# LMNC_VCO_-_v1_2.net
KiCad netlist of a schematic drawn in EAGLE
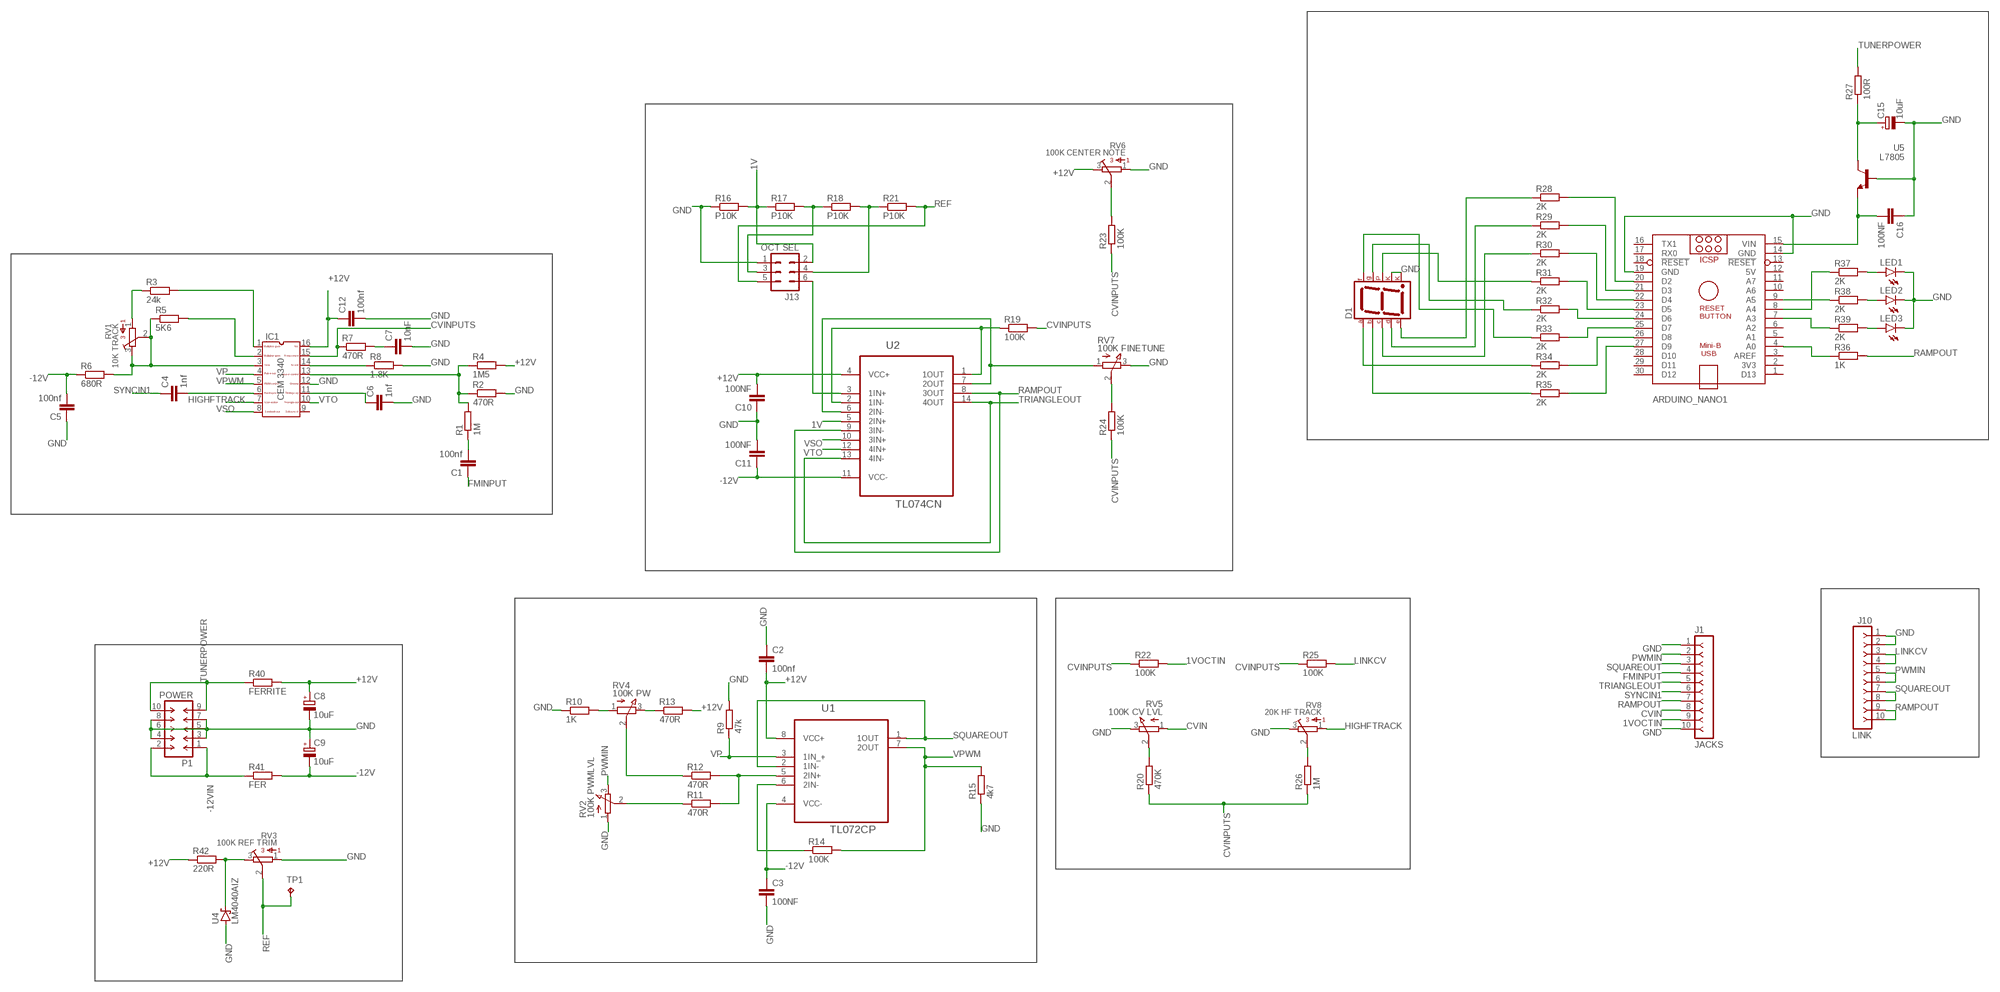
[diagram p0: schematic, sheet 1]

(export (version "E")
  (design (tool "Eeschema 10.0.6"))
  (components
    (comp (ref "ARDUINO_NANO1")
      (value "ARDUINO_NANO")
      (footprint "eagle-import:ARDUINO_NANO")
      (libsource (lib "eagle-import") (part "ARDUINO_NANO"))
    )
    (comp (ref "C1")
      (value "100nf")
      (footprint "eagle-import:C2.5-3")
      (libsource (lib "eagle-import") (part "C2,5-3"))
    )
    (comp (ref "C2")
      (value "100nf")
      (footprint "eagle-import:C2.5-3")
      (libsource (lib "eagle-import") (part "C2,5-3"))
    )
    (comp (ref "C3")
      (value "100NF")
      (footprint "eagle-import:C2.5-3")
      (libsource (lib "eagle-import") (part "C2,5-3"))
    )
    (comp (ref "C4")
      (value "1nf")
      (footprint "eagle-import:C2.5-3")
      (libsource (lib "eagle-import") (part "C2,5-3"))
    )
    (comp (ref "C5")
      (value "100nf")
      (footprint "eagle-import:C2.5-3")
      (libsource (lib "eagle-import") (part "C2,5-3"))
    )
    (comp (ref "C6")
      (value "1nf")
      (footprint "eagle-import:C2.5-3")
      (libsource (lib "eagle-import") (part "C2,5-3"))
    )
    (comp (ref "C7")
      (value "10nF")
      (footprint "eagle-import:C2.5-3")
      (libsource (lib "eagle-import") (part "C2,5-3"))
    )
    (comp (ref "C8")
      (value "10uF")
      (footprint "eagle-import:E2,5-5")
      (libsource (lib "eagle-import") (part "CPOL-EUE2.5-5"))
    )
    (comp (ref "C9")
      (value "10uF")
      (footprint "eagle-import:E2,5-5")
      (libsource (lib "eagle-import") (part "CPOL-EUE2.5-5"))
    )
    (comp (ref "C10")
      (value "100NF")
      (footprint "eagle-import:C2.5-3")
      (libsource (lib "eagle-import") (part "C2,5-3"))
    )
    (comp (ref "C11")
      (value "100NF")
      (footprint "eagle-import:C2.5-3")
      (libsource (lib "eagle-import") (part "C2,5-3"))
    )
    (comp (ref "C12")
      (value "100nf")
      (footprint "eagle-import:C2.5-3")
      (libsource (lib "eagle-import") (part "C2,5-3"))
    )
    (comp (ref "C15")
      (value "10uF")
      (footprint "eagle-import:E2,5-5")
      (libsource (lib "eagle-import") (part "CPOL-EUE2.5-5"))
    )
    (comp (ref "C16")
      (value "100NF")
      (footprint "eagle-import:C2.5-3")
      (libsource (lib "eagle-import") (part "C2,5-3"))
    )
    (comp (ref "D1")
      (value "7SEG-CK")
      (footprint "eagle-import:7SEG-13")
      (libsource (lib "eagle-import") (part "7SEG-CK"))
    )
    (comp (ref "IC1")
      (value "CEM3340")
      (footprint "eagle-import:DIL16")
      (libsource (lib "eagle-import") (part "CEM3340"))
    )
    (comp (ref "J1")
      (value "JACKS")
      (footprint "eagle-import:SIP-100-10-32Y")
      (fields (field (name "SPICEPREFIX") "X"))
      (libsource (lib "eagle-import") (part "F-1X10-SIP-100-32Y"))
    )
    (comp (ref "J10")
      (value "LINK")
      (footprint "eagle-import:SIP-100-10-32Y")
      (libsource (lib "eagle-import") (part "F-1X10-SIP-100-32Y"))
    )
    (comp (ref "J13")
      (value "OCT SEL")
      (footprint "eagle-import:MA03-2")
      (libsource (lib "eagle-import") (part "MA03-2"))
    )
    (comp (ref "LED1")
      (value "LED3MM")
      (footprint "eagle-import:LED3MM")
      (libsource (lib "eagle-import") (part "LED3MM"))
    )
    (comp (ref "LED2")
      (value "LED3MM")
      (footprint "eagle-import:LED3MM")
      (libsource (lib "eagle-import") (part "LED3MM"))
    )
    (comp (ref "LED3")
      (value "LED3MM")
      (footprint "eagle-import:LED3MM")
      (libsource (lib "eagle-import") (part "LED3MM"))
    )
    (comp (ref "P1")
      (value "POWER")
      (footprint "eagle-import:DIL-100-2X05")
      (libsource (lib "eagle-import") (part "M-2X05-DIL-100"))
    )
    (comp (ref "R1")
      (value "1M")
      (footprint "eagle-import:0207_10")
      (libsource (lib "eagle-import") (part "R-EU_0207/10"))
    )
    (comp (ref "R2")
      (value "470R")
      (footprint "eagle-import:0207_10")
      (libsource (lib "eagle-import") (part "R-EU_0207/10"))
    )
    (comp (ref "R3")
      (value "24k")
      (footprint "eagle-import:0207_10")
      (libsource (lib "eagle-import") (part "R-EU_0207/10"))
    )
    (comp (ref "R4")
      (value "1M5")
      (footprint "eagle-import:0207_10")
      (libsource (lib "eagle-import") (part "R-EU_0207/10"))
    )
    (comp (ref "R5")
      (value "5K6")
      (footprint "eagle-import:0207_10")
      (libsource (lib "eagle-import") (part "R-EU_0207/10"))
    )
    (comp (ref "R6")
      (value "680R")
      (footprint "eagle-import:0207_10")
      (libsource (lib "eagle-import") (part "R-EU_0207/10"))
    )
    (comp (ref "R7")
      (value "470R")
      (footprint "eagle-import:0207_10")
      (libsource (lib "eagle-import") (part "R-EU_0207/10"))
    )
    (comp (ref "R8")
      (value "1.8K")
      (footprint "eagle-import:0207_10")
      (libsource (lib "eagle-import") (part "R-EU_0207/10"))
    )
    (comp (ref "R9")
      (value "47k")
      (footprint "eagle-import:0207_10")
      (libsource (lib "eagle-import") (part "R-EU_0207/10"))
    )
    (comp (ref "R10")
      (value "1K")
      (footprint "eagle-import:0207_10")
      (libsource (lib "eagle-import") (part "R-EU_0207/10"))
    )
    (comp (ref "R11")
      (value "470R")
      (footprint "eagle-import:0207_10")
      (libsource (lib "eagle-import") (part "R-EU_0207/10"))
    )
    (comp (ref "R12")
      (value "470R")
      (footprint "eagle-import:0207_10")
      (libsource (lib "eagle-import") (part "R-EU_0207/10"))
    )
    (comp (ref "R13")
      (value "470R")
      (footprint "eagle-import:0207_10")
      (libsource (lib "eagle-import") (part "R-EU_0207/10"))
    )
    (comp (ref "R14")
      (value "100K")
      (footprint "eagle-import:0207_10")
      (libsource (lib "eagle-import") (part "R-EU_0207/10"))
    )
    (comp (ref "R15")
      (value "4k7")
      (footprint "eagle-import:0207_10")
      (libsource (lib "eagle-import") (part "R-EU_0207/10"))
    )
    (comp (ref "R16")
      (value "P10K")
      (footprint "eagle-import:0207_10")
      (libsource (lib "eagle-import") (part "R-EU_0207/10"))
    )
    (comp (ref "R17")
      (value "P10K")
      (footprint "eagle-import:0207_10")
      (libsource (lib "eagle-import") (part "R-EU_0207/10"))
    )
    (comp (ref "R18")
      (value "P10K")
      (footprint "eagle-import:0207_10")
      (libsource (lib "eagle-import") (part "R-EU_0207/10"))
    )
    (comp (ref "R19")
      (value "100K")
      (footprint "eagle-import:0207_10")
      (libsource (lib "eagle-import") (part "R-EU_0207/10"))
    )
    (comp (ref "R20")
      (value "470K")
      (footprint "eagle-import:0207_10")
      (libsource (lib "eagle-import") (part "R-EU_0207/10"))
    )
    (comp (ref "R21")
      (value "P10K")
      (footprint "eagle-import:0207_10")
      (libsource (lib "eagle-import") (part "R-EU_0207/10"))
    )
    (comp (ref "R22")
      (value "100K")
      (footprint "eagle-import:0207_10")
      (libsource (lib "eagle-import") (part "R-EU_0207/10"))
    )
    (comp (ref "R23")
      (value "100K")
      (footprint "eagle-import:0207_10")
      (libsource (lib "eagle-import") (part "R-EU_0207/10"))
    )
    (comp (ref "R24")
      (value "100K")
      (footprint "eagle-import:0207_10")
      (libsource (lib "eagle-import") (part "R-EU_0207/10"))
    )
    (comp (ref "R25")
      (value "100K")
      (footprint "eagle-import:0207_10")
      (libsource (lib "eagle-import") (part "R-EU_0207/10"))
    )
    (comp (ref "R26")
      (value "1M")
      (footprint "eagle-import:0207_10")
      (libsource (lib "eagle-import") (part "R-EU_0207/10"))
    )
    (comp (ref "R27")
      (value "100R")
      (footprint "eagle-import:0207_10")
      (libsource (lib "eagle-import") (part "R-EU_0207/10"))
    )
    (comp (ref "R28")
      (value "2K")
      (footprint "eagle-import:0207_10")
      (libsource (lib "eagle-import") (part "R-EU_0207/10"))
    )
    (comp (ref "R29")
      (value "2K")
      (footprint "eagle-import:0207_10")
      (libsource (lib "eagle-import") (part "R-EU_0207/10"))
    )
    (comp (ref "R30")
      (value "2K")
      (footprint "eagle-import:0207_10")
      (libsource (lib "eagle-import") (part "R-EU_0207/10"))
    )
    (comp (ref "R31")
      (value "2K")
      (footprint "eagle-import:0207_10")
      (libsource (lib "eagle-import") (part "R-EU_0207/10"))
    )
    (comp (ref "R32")
      (value "2K")
      (footprint "eagle-import:0207_10")
      (libsource (lib "eagle-import") (part "R-EU_0207/10"))
    )
    (comp (ref "R33")
      (value "2K")
      (footprint "eagle-import:0207_10")
      (libsource (lib "eagle-import") (part "R-EU_0207/10"))
    )
    (comp (ref "R34")
      (value "2K")
      (footprint "eagle-import:0207_10")
      (libsource (lib "eagle-import") (part "R-EU_0207/10"))
    )
    (comp (ref "R35")
      (value "2K")
      (footprint "eagle-import:0207_10")
      (libsource (lib "eagle-import") (part "R-EU_0207/10"))
    )
    (comp (ref "R36")
      (value "1K")
      (footprint "eagle-import:0207_10")
      (libsource (lib "eagle-import") (part "R-EU_0207/10"))
    )
    (comp (ref "R37")
      (value "2K")
      (footprint "eagle-import:0207_10")
      (libsource (lib "eagle-import") (part "R-EU_0207/10"))
    )
    (comp (ref "R38")
      (value "2K")
      (footprint "eagle-import:0207_10")
      (libsource (lib "eagle-import") (part "R-EU_0207/10"))
    )
    (comp (ref "R39")
      (value "2K")
      (footprint "eagle-import:0207_10")
      (libsource (lib "eagle-import") (part "R-EU_0207/10"))
    )
    (comp (ref "R40")
      (value "FERRITE")
      (footprint "eagle-import:0207_10")
      (libsource (lib "eagle-import") (part "R-EU_0207/10"))
    )
    (comp (ref "R41")
      (value "FER")
      (footprint "eagle-import:0207_10")
      (libsource (lib "eagle-import") (part "R-EU_0207/10"))
    )
    (comp (ref "R42")
      (value "220R")
      (footprint "eagle-import:0207_10")
      (libsource (lib "eagle-import") (part "R-EU_0207/10"))
    )
    (comp (ref "RV1")
      (value "10K TRACK")
      (footprint "eagle-import:3386W")
      (libsource (lib "eagle-import") (part "3386-W"))
    )
    (comp (ref "RV2")
      (value "100K PWMLVL")
      (footprint "eagle-import:EVUF")
      (libsource (lib "eagle-import") (part "EVUAF2"))
    )
    (comp (ref "RV3")
      (value "100K REF TRIM")
      (footprint "eagle-import:3386W")
      (libsource (lib "eagle-import") (part "3386-W"))
    )
    (comp (ref "RV4")
      (value "100K PW")
      (footprint "eagle-import:EVUF")
      (libsource (lib "eagle-import") (part "EVUAF2"))
    )
    (comp (ref "RV5")
      (value "100K CV LVL")
      (footprint "eagle-import:EVUF")
      (libsource (lib "eagle-import") (part "EVUAF2"))
    )
    (comp (ref "RV6")
      (value "100K CENTER NOTE")
      (footprint "eagle-import:3386W")
      (libsource (lib "eagle-import") (part "3386-W"))
    )
    (comp (ref "RV7")
      (value "100K FINETUNE")
      (footprint "eagle-import:EVUF")
      (libsource (lib "eagle-import") (part "EVUAF2"))
    )
    (comp (ref "RV8")
      (value "20K HF TRACK")
      (footprint "eagle-import:3386W")
      (libsource (lib "eagle-import") (part "3386-W"))
    )
    (comp (ref "TP1")
      (value "4v")
      (footprint "eagle-import:B2,54")
      (libsource (lib "eagle-import") (part "TPB2,54"))
    )
    (comp (ref "U1")
      (value "TL072CP")
      (footprint "eagle-import:DIP254P762X508-8")
      (fields (field (name "MF") "Texas Instruments"))
      (libsource (lib "eagle-import") (part "TL072CP"))
    )
    (comp (ref "U2")
      (value "TL074CN")
      (footprint "eagle-import:DIP254P762X508-14")
      (fields (field (name "MF") "STMicroelectronics"))
      (libsource (lib "eagle-import") (part "TL074CN"))
    )
    (comp (ref "U4")
      (value "LM4040AIZ")
      (footprint "eagle-import:SOT54A")
      (libsource (lib "eagle-import") (part "SCHOTTKY-DIODE"))
    )
    (comp (ref "U5")
      (value "L7805")
      (footprint "eagle-import:TO220BV")
      (libsource (lib "eagle-import") (part "2SC1306"))
    )
  )
  (nets
    (net (code "1") (name "+12V") (class "Default")
      (node (ref "C10") (pin "2") (pinfunction "2_2") (pintype "passive"))
      (node (ref "C12") (pin "1") (pinfunction "1_1") (pintype "passive"))
      (node (ref "C2") (pin "2") (pinfunction "2_2") (pintype "passive"))
      (node (ref "C8") (pin "+") (pinfunction "+_+") (pintype "passive"))
      (node (ref "IC1") (pin "16") (pinfunction "16_16") (pintype "power_in"))
      (node (ref "R13") (pin "2") (pinfunction "2_2") (pintype "passive"))
      (node (ref "R4") (pin "2") (pinfunction "2_2") (pintype "passive"))
      (node (ref "R40") (pin "2") (pinfunction "2_2") (pintype "passive"))
      (node (ref "R42") (pin "1") (pinfunction "1_1") (pintype "passive"))
      (node (ref "RV6") (pin "3") (pinfunction "3_3") (pintype "passive"))
      (node (ref "U1") (pin "8") (pinfunction "VCC+_8") (pintype "power_in"))
      (node (ref "U2") (pin "4") (pinfunction "VCC+_4") (pintype "power_in"))
    )
    (net (code "2") (name "-12V") (class "Default")
      (node (ref "C11") (pin "1") (pinfunction "1_1") (pintype "passive"))
      (node (ref "C3") (pin "1") (pinfunction "1_1") (pintype "passive"))
      (node (ref "C5") (pin "2") (pinfunction "2_2") (pintype "passive"))
      (node (ref "C9") (pin "-") (pinfunction "-_-") (pintype "passive"))
      (node (ref "R41") (pin "2") (pinfunction "2_2") (pintype "passive"))
      (node (ref "R6") (pin "1") (pinfunction "1_1") (pintype "passive"))
      (node (ref "U1") (pin "4") (pinfunction "VCC-_4") (pintype "passive"))
      (node (ref "U2") (pin "11") (pinfunction "VCC-_11") (pintype "power_in"))
    )
    (net (code "3") (name "-12VIN") (class "Default")
      (node (ref "P1") (pin "1") (pinfunction "1_1") (pintype "passive"))
      (node (ref "P1") (pin "2") (pinfunction "2_2") (pintype "passive"))
      (node (ref "R41") (pin "1") (pinfunction "1_1") (pintype "passive"))
    )
    (net (code "4") (name "1V") (class "Default")
      (node (ref "J13") (pin "2") (pinfunction "2_2") (pintype "passive"))
      (node (ref "R16") (pin "2") (pinfunction "2_2") (pintype "passive"))
      (node (ref "R17") (pin "1") (pinfunction "1_1") (pintype "passive"))
      (node (ref "U2") (pin "5") (pinfunction "2IN+_5") (pintype "input"))
    )
    (net (code "5") (name "1VOCTIN") (class "Default")
      (node (ref "J1") (pin "9") (pinfunction "9_9") (pintype "passive"))
      (node (ref "R22") (pin "2") (pinfunction "2_2") (pintype "passive"))
    )
    (net (code "6") (name "5V") (class "Default")
      (node (ref "ARDUINO_NANO1") (pin "12") (pinfunction "5V_12") (pintype "power_in"))
    )
    (net (code "7") (name "CVIN") (class "Default")
      (node (ref "J1") (pin "8") (pinfunction "8_8") (pintype "passive"))
      (node (ref "RV5") (pin "1") (pinfunction "A_1") (pintype "passive"))
    )
    (net (code "8") (name "CVINPUTS") (class "Default")
      (node (ref "IC1") (pin "15") (pinfunction "15_15") (pintype "input"))
      (node (ref "R19") (pin "2") (pinfunction "2_2") (pintype "passive"))
      (node (ref "R20") (pin "1") (pinfunction "1_1") (pintype "passive"))
      (node (ref "R22") (pin "1") (pinfunction "1_1") (pintype "passive"))
      (node (ref "R23") (pin "1") (pinfunction "1_1") (pintype "passive"))
      (node (ref "R24") (pin "1") (pinfunction "1_1") (pintype "passive"))
      (node (ref "R25") (pin "1") (pinfunction "1_1") (pintype "passive"))
      (node (ref "R26") (pin "1") (pinfunction "1_1") (pintype "passive"))
      (node (ref "R7") (pin "1") (pinfunction "1_1") (pintype "passive"))
    )
    (net (code "9") (name "FMINPUT") (class "Default")
      (node (ref "C1") (pin "1") (pinfunction "1_1") (pintype "passive"))
      (node (ref "J1") (pin "4") (pinfunction "4_4") (pintype "passive"))
    )
    (net (code "10") (name "GND") (class "Default")
      (node (ref "ARDUINO_NANO1") (pin "14") (pinfunction "GND_14") (pintype "power_in"))
      (node (ref "ARDUINO_NANO1") (pin "19") (pinfunction "GND_19") (pintype "power_in"))
      (node (ref "C10") (pin "1") (pinfunction "1_1") (pintype "passive"))
      (node (ref "C11") (pin "2") (pinfunction "2_2") (pintype "passive"))
      (node (ref "C12") (pin "2") (pinfunction "2_2") (pintype "passive"))
      (node (ref "C15") (pin "-") (pinfunction "-_-") (pintype "passive"))
      (node (ref "C16") (pin "1") (pinfunction "1_1") (pintype "passive"))
      (node (ref "C2") (pin "1") (pinfunction "1_1") (pintype "passive"))
      (node (ref "C3") (pin "2") (pinfunction "2_2") (pintype "passive"))
      (node (ref "C5") (pin "1") (pinfunction "1_1") (pintype "passive"))
      (node (ref "C6") (pin "2") (pinfunction "2_2") (pintype "passive"))
      (node (ref "C7") (pin "2") (pinfunction "2_2") (pintype "passive"))
      (node (ref "C8") (pin "-") (pinfunction "-_-") (pintype "passive"))
      (node (ref "C9") (pin "+") (pinfunction "+_+") (pintype "passive"))
      (node (ref "D1") (pin "3") (pinfunction "CK1_3") (pintype "passive"))
      (node (ref "D1") (pin "8") (pinfunction "CK2_8") (pintype "passive"))
      (node (ref "IC1") (pin "12") (pinfunction "12_12") (pintype "power_in"))
      (node (ref "J1") (pin "1") (pinfunction "1_1") (pintype "passive"))
      (node (ref "J1") (pin "10") (pinfunction "10_10") (pintype "passive"))
      (node (ref "J10") (pin "1") (pinfunction "1_1") (pintype "passive"))
      (node (ref "J10") (pin "2") (pinfunction "2_2") (pintype "passive"))
      (node (ref "J13") (pin "1") (pinfunction "1_1") (pintype "passive"))
      (node (ref "LED1") (pin "K") (pinfunction "C_K") (pintype "passive"))
      (node (ref "LED2") (pin "K") (pinfunction "C_K") (pintype "passive"))
      (node (ref "LED3") (pin "K") (pinfunction "C_K") (pintype "passive"))
      (node (ref "P1") (pin "3") (pinfunction "3_3") (pintype "passive"))
      (node (ref "P1") (pin "4") (pinfunction "4_4") (pintype "passive"))
      (node (ref "P1") (pin "5") (pinfunction "5_5") (pintype "passive"))
      (node (ref "P1") (pin "6") (pinfunction "6_6") (pintype "passive"))
      (node (ref "P1") (pin "7") (pinfunction "7_7") (pintype "passive"))
      (node (ref "P1") (pin "8") (pinfunction "8_8") (pintype "passive"))
      (node (ref "R10") (pin "1") (pinfunction "1_1") (pintype "passive"))
      (node (ref "R15") (pin "1") (pinfunction "1_1") (pintype "passive"))
      (node (ref "R16") (pin "1") (pinfunction "1_1") (pintype "passive"))
      (node (ref "R2") (pin "2") (pinfunction "2_2") (pintype "passive"))
      (node (ref "R8") (pin "2") (pinfunction "2_2") (pintype "passive"))
      (node (ref "R9") (pin "2") (pinfunction "2_2") (pintype "passive"))
      (node (ref "RV2") (pin "1") (pinfunction "A_1") (pintype "passive"))
      (node (ref "RV3") (pin "1") (pinfunction "1_1") (pintype "passive"))
      (node (ref "RV5") (pin "3") (pinfunction "E_3") (pintype "passive"))
      (node (ref "RV6") (pin "1") (pinfunction "1_1") (pintype "passive"))
      (node (ref "RV7") (pin "3") (pinfunction "E_3") (pintype "passive"))
      (node (ref "RV8") (pin "3") (pinfunction "3_3") (pintype "passive"))
      (node (ref "U4") (pin "A1") (pinfunction "A_A1") (pintype "passive"))
      (node (ref "U5") (pin "1") (pinfunction "B_1") (pintype "passive"))
    )
    (net (code "11") (name "HIGHFTRACK") (class "Default")
      (node (ref "IC1") (pin "7") (pinfunction "7_7") (pintype "bidirectional"))
      (node (ref "RV8") (pin "1") (pinfunction "1_1") (pintype "passive"))
    )
    (net (code "12") (name "LINKCV") (class "Default")
      (node (ref "J10") (pin "3") (pinfunction "3_3") (pintype "passive"))
      (node (ref "J10") (pin "4") (pinfunction "4_4") (pintype "passive"))
      (node (ref "R25") (pin "2") (pinfunction "2_2") (pintype "passive"))
    )
    (net (code "13") (name "Net-(ARDUINO_NANO1-A0)") (class "Default")
      (node (ref "ARDUINO_NANO1") (pin "4") (pinfunction "A0_4") (pintype "bidirectional"))
      (node (ref "R36") (pin "1") (pinfunction "1_1") (pintype "passive"))
    )
    (net (code "14") (name "Net-(ARDUINO_NANO1-A3)") (class "Default")
      (node (ref "ARDUINO_NANO1") (pin "7") (pinfunction "A3_7") (pintype "bidirectional"))
      (node (ref "R39") (pin "1") (pinfunction "1_1") (pintype "passive"))
    )
    (net (code "15") (name "Net-(ARDUINO_NANO1-A4)") (class "Default")
      (node (ref "ARDUINO_NANO1") (pin "8") (pinfunction "A4_8") (pintype "bidirectional"))
      (node (ref "R37") (pin "1") (pinfunction "1_1") (pintype "passive"))
    )
    (net (code "16") (name "Net-(ARDUINO_NANO1-A5)") (class "Default")
      (node (ref "ARDUINO_NANO1") (pin "9") (pinfunction "A5_9") (pintype "bidirectional"))
      (node (ref "R38") (pin "1") (pinfunction "1_1") (pintype "passive"))
    )
    (net (code "17") (name "Net-(ARDUINO_NANO1-D2)") (class "Default")
      (node (ref "ARDUINO_NANO1") (pin "20") (pinfunction "D2_20") (pintype "bidirectional"))
      (node (ref "R28") (pin "2") (pinfunction "2_2") (pintype "passive"))
    )
    (net (code "18") (name "Net-(ARDUINO_NANO1-D3)") (class "Default")
      (node (ref "ARDUINO_NANO1") (pin "21") (pinfunction "D3_21") (pintype "bidirectional"))
      (node (ref "R29") (pin "2") (pinfunction "2_2") (pintype "passive"))
    )
    (net (code "19") (name "Net-(ARDUINO_NANO1-D4)") (class "Default")
      (node (ref "ARDUINO_NANO1") (pin "22") (pinfunction "D4_22") (pintype "bidirectional"))
      (node (ref "R30") (pin "2") (pinfunction "2_2") (pintype "passive"))
    )
    (net (code "20") (name "Net-(ARDUINO_NANO1-D5)") (class "Default")
      (node (ref "ARDUINO_NANO1") (pin "23") (pinfunction "D5_23") (pintype "bidirectional"))
      (node (ref "R31") (pin "2") (pinfunction "2_2") (pintype "passive"))
    )
    (net (code "21") (name "Net-(ARDUINO_NANO1-D6)") (class "Default")
      (node (ref "ARDUINO_NANO1") (pin "24") (pinfunction "D6_24") (pintype "bidirectional"))
      (node (ref "R32") (pin "2") (pinfunction "2_2") (pintype "passive"))
    )
    (net (code "22") (name "Net-(ARDUINO_NANO1-D7)") (class "Default")
      (node (ref "ARDUINO_NANO1") (pin "25") (pinfunction "D7_25") (pintype "bidirectional"))
      (node (ref "R33") (pin "2") (pinfunction "2_2") (pintype "passive"))
    )
    (net (code "23") (name "Net-(ARDUINO_NANO1-D8)") (class "Default")
      (node (ref "ARDUINO_NANO1") (pin "26") (pinfunction "D8_26") (pintype "bidirectional"))
      (node (ref "R34") (pin "2") (pinfunction "2_2") (pintype "passive"))
    )
    (net (code "24") (name "Net-(ARDUINO_NANO1-D9)") (class "Default")
      (node (ref "ARDUINO_NANO1") (pin "27") (pinfunction "D9_27") (pintype "bidirectional"))
      (node (ref "R35") (pin "2") (pinfunction "2_2") (pintype "passive"))
    )
    (net (code "25") (name "Net-(ARDUINO_NANO1-VIN)") (class "Default")
      (node (ref "ARDUINO_NANO1") (pin "15") (pinfunction "VIN_15") (pintype "power_in"))
      (node (ref "C16") (pin "2") (pinfunction "2_2") (pintype "passive"))
      (node (ref "U5") (pin "3") (pinfunction "E_3") (pintype "passive"))
    )
    (net (code "26") (name "Net-(C1-Pad2)") (class "Default")
      (node (ref "C1") (pin "2") (pinfunction "2_2") (pintype "passive"))
      (node (ref "R1") (pin "1") (pinfunction "1_1") (pintype "passive"))
    )
    (net (code "27") (name "Net-(C4-Pad2)") (class "Default")
      (node (ref "C4") (pin "2") (pinfunction "2_2") (pintype "passive"))
      (node (ref "IC1") (pin "6") (pinfunction "6_6") (pintype "input"))
    )
    (net (code "28") (name "Net-(C6-Pad1)") (class "Default")
      (node (ref "C6") (pin "1") (pinfunction "1_1") (pintype "passive"))
      (node (ref "IC1") (pin "11") (pinfunction "11_11") (pintype "bidirectional"))
    )
    (net (code "29") (name "Net-(C7-Pad1)") (class "Default")
      (node (ref "C7") (pin "1") (pinfunction "1_1") (pintype "passive"))
      (node (ref "R7") (pin "2") (pinfunction "2_2") (pintype "passive"))
    )
    (net (code "30") (name "Net-(D1-A)") (class "Default")
      (node (ref "D1") (pin "7") (pinfunction "A_7") (pintype "passive"))
      (node (ref "R34") (pin "1") (pinfunction "1_1") (pintype "passive"))
    )
    (net (code "31") (name "Net-(D1-B)") (class "Default")
      (node (ref "D1") (pin "6") (pinfunction "B_6") (pintype "passive"))
      (node (ref "R35") (pin "1") (pinfunction "1_1") (pintype "passive"))
    )
    (net (code "32") (name "Net-(D1-C)") (class "Default")
      (node (ref "D1") (pin "4") (pinfunction "C_4") (pintype "passive"))
      (node (ref "R30") (pin "1") (pinfunction "1_1") (pintype "passive"))
    )
    (net (code "33") (name "Net-(D1-D)") (class "Default")
      (node (ref "D1") (pin "2") (pinfunction "D_2") (pintype "passive"))
      (node (ref "R29") (pin "1") (pinfunction "1_1") (pintype "passive"))
    )
    (net (code "34") (name "Net-(D1-DP)") (class "Default")
      (node (ref "D1") (pin "5") (pinfunction "DP_5") (pintype "passive"))
      (node (ref "R31") (pin "1") (pinfunction "1_1") (pintype "passive"))
    )
    (net (code "35") (name "Net-(D1-E)") (class "Default")
      (node (ref "D1") (pin "1") (pinfunction "E_1") (pintype "passive"))
      (node (ref "R28") (pin "1") (pinfunction "1_1") (pintype "passive"))
    )
    (net (code "36") (name "Net-(D1-F)") (class "Default")
      (node (ref "D1") (pin "9") (pinfunction "F_9") (pintype "passive"))
      (node (ref "R33") (pin "1") (pinfunction "1_1") (pintype "passive"))
    )
    (net (code "37") (name "Net-(D1-G)") (class "Default")
      (node (ref "D1") (pin "10") (pinfunction "G_10") (pintype "passive"))
      (node (ref "R32") (pin "1") (pinfunction "1_1") (pintype "passive"))
    )
    (net (code "38") (name "Net-(IC1-Pad1)") (class "Default")
      (node (ref "IC1") (pin "1") (pinfunction "1_1") (pintype "bidirectional"))
      (node (ref "R3") (pin "2") (pinfunction "2_2") (pintype "passive"))
    )
    (net (code "39") (name "Net-(IC1-Pad2)") (class "Default")
      (node (ref "IC1") (pin "2") (pinfunction "2_2") (pintype "bidirectional"))
      (node (ref "R5") (pin "2") (pinfunction "2_2") (pintype "passive"))
    )
    (net (code "40") (name "Net-(IC1-Pad3)") (class "Default")
      (node (ref "IC1") (pin "3") (pinfunction "3_3") (pintype "power_in"))
      (node (ref "R5") (pin "1") (pinfunction "1_1") (pintype "passive"))
      (node (ref "R6") (pin "2") (pinfunction "2_2") (pintype "passive"))
      (node (ref "RV1") (pin "2") (pinfunction "2_2") (pintype "passive"))
      (node (ref "RV1") (pin "3") (pinfunction "3_3") (pintype "passive"))
    )
    (net (code "41") (name "Net-(IC1-Pad13)") (class "Default")
      (node (ref "IC1") (pin "13") (pinfunction "13_13") (pintype "input"))
      (node (ref "R1") (pin "2") (pinfunction "2_2") (pintype "passive"))
      (node (ref "R2") (pin "1") (pinfunction "1_1") (pintype "passive"))
      (node (ref "R4") (pin "1") (pinfunction "1_1") (pintype "passive"))
    )
    (net (code "42") (name "Net-(IC1-Pad14)") (class "Default")
      (node (ref "IC1") (pin "14") (pinfunction "14_14") (pintype "input"))
      (node (ref "R8") (pin "1") (pinfunction "1_1") (pintype "passive"))
    )
    (net (code "43") (name "Net-(J13-Pad3)") (class "Default")
      (node (ref "J13") (pin "3") (pinfunction "3_3") (pintype "passive"))
      (node (ref "R17") (pin "2") (pinfunction "2_2") (pintype "passive"))
      (node (ref "R18") (pin "1") (pinfunction "1_1") (pintype "passive"))
    )
    (net (code "44") (name "Net-(J13-Pad4)") (class "Default")
      (node (ref "J13") (pin "4") (pinfunction "4_4") (pintype "passive"))
      (node (ref "R18") (pin "2") (pinfunction "2_2") (pintype "passive"))
      (node (ref "R21") (pin "1") (pinfunction "1_1") (pintype "passive"))
    )
    (net (code "45") (name "Net-(LED1-PadA)") (class "Default")
      (node (ref "LED1") (pin "A") (pinfunction "A_A") (pintype "passive"))
      (node (ref "R37") (pin "2") (pinfunction "2_2") (pintype "passive"))
    )
    (net (code "46") (name "Net-(LED2-PadA)") (class "Default")
      (node (ref "LED2") (pin "A") (pinfunction "A_A") (pintype "passive"))
      (node (ref "R38") (pin "2") (pinfunction "2_2") (pintype "passive"))
    )
    (net (code "47") (name "Net-(LED3-PadA)") (class "Default")
      (node (ref "LED3") (pin "A") (pinfunction "A_A") (pintype "passive"))
      (node (ref "R39") (pin "2") (pinfunction "2_2") (pintype "passive"))
    )
    (net (code "48") (name "Net-(R3-Pad1)") (class "Default")
      (node (ref "R3") (pin "1") (pinfunction "1_1") (pintype "passive"))
      (node (ref "RV1") (pin "1") (pinfunction "1_1") (pintype "passive"))
    )
    (net (code "49") (name "Net-(R23-Pad2)") (class "Default")
      (node (ref "R23") (pin "2") (pinfunction "2_2") (pintype "passive"))
      (node (ref "RV6") (pin "2") (pinfunction "2_2") (pintype "passive"))
    )
    (net (code "50") (name "Net-(R26-Pad2)") (class "Default")
      (node (ref "R26") (pin "2") (pinfunction "2_2") (pintype "passive"))
      (node (ref "RV8") (pin "2") (pinfunction "2_2") (pintype "passive"))
    )
    (net (code "51") (name "Net-(RV2-S)") (class "Default")
      (node (ref "R11") (pin "1") (pinfunction "1_1") (pintype "passive"))
      (node (ref "RV2") (pin "2") (pinfunction "S_2") (pintype "passive"))
    )
    (net (code "52") (name "Net-(RV4-A)") (class "Default")
      (node (ref "R10") (pin "2") (pinfunction "2_2") (pintype "passive"))
      (node (ref "RV4") (pin "1") (pinfunction "A_1") (pintype "passive"))
    )
    (net (code "53") (name "Net-(RV4-E)") (class "Default")
      (node (ref "R13") (pin "1") (pinfunction "1_1") (pintype "passive"))
      (node (ref "RV4") (pin "3") (pinfunction "E_3") (pintype "passive"))
    )
    (net (code "54") (name "Net-(RV4-S)") (class "Default")
      (node (ref "R12") (pin "1") (pinfunction "1_1") (pintype "passive"))
      (node (ref "RV4") (pin "2") (pinfunction "S_2") (pintype "passive"))
    )
    (net (code "55") (name "Net-(RV5-S)") (class "Default")
      (node (ref "R20") (pin "2") (pinfunction "2_2") (pintype "passive"))
      (node (ref "RV5") (pin "2") (pinfunction "S_2") (pintype "passive"))
    )
    (net (code "56") (name "Net-(RV7-A)") (class "Default")
      (node (ref "RV7") (pin "1") (pinfunction "A_1") (pintype "passive"))
      (node (ref "U2") (pin "6") (pinfunction "2IN-_6") (pintype "input"))
      (node (ref "U2") (pin "7") (pinfunction "2OUT_7") (pintype "output"))
    )
    (net (code "57") (name "Net-(RV7-S)") (class "Default")
      (node (ref "R24") (pin "2") (pinfunction "2_2") (pintype "passive"))
      (node (ref "RV7") (pin "2") (pinfunction "S_2") (pintype "passive"))
    )
    (net (code "58") (name "Net-(U1-2IN+)") (class "Default")
      (node (ref "R11") (pin "2") (pinfunction "2_2") (pintype "passive"))
      (node (ref "R12") (pin "2") (pinfunction "2_2") (pintype "passive"))
      (node (ref "U1") (pin "5") (pinfunction "2IN+_5") (pintype "input"))
    )
    (net (code "59") (name "Net-(U1-2IN-)") (class "Default")
      (node (ref "R14") (pin "1") (pinfunction "1_1") (pintype "passive"))
      (node (ref "U1") (pin "6") (pinfunction "2IN-_6") (pintype "input"))
    )
    (net (code "60") (name "Net-(U2-1IN+)") (class "Default")
      (node (ref "J13") (pin "6") (pinfunction "6_6") (pintype "passive"))
      (node (ref "U2") (pin "3") (pinfunction "1IN+_3") (pintype "input"))
    )
    (net (code "61") (name "Net-(U2-1IN-)") (class "Default")
      (node (ref "R19") (pin "1") (pinfunction "1_1") (pintype "passive"))
      (node (ref "U2") (pin "1") (pinfunction "1OUT_1") (pintype "output"))
      (node (ref "U2") (pin "2") (pinfunction "1IN-_2") (pintype "input"))
    )
    (net (code "62") (name "Net-(U4-C)") (class "Default")
      (node (ref "R42") (pin "2") (pinfunction "2_2") (pintype "passive"))
      (node (ref "RV3") (pin "3") (pinfunction "3_3") (pintype "passive"))
      (node (ref "U4") (pin "A2") (pinfunction "C_A2") (pintype "passive"))
    )
    (net (code "63") (name "Net-(U5-C)") (class "Default")
      (node (ref "C15") (pin "+") (pinfunction "+_+") (pintype "passive"))
      (node (ref "R27") (pin "1") (pinfunction "1_1") (pintype "passive"))
      (node (ref "U5") (pin "2") (pinfunction "C_2") (pintype "passive"))
    )
    (net (code "64") (name "PWMIN") (class "Default")
      (node (ref "J1") (pin "2") (pinfunction "2_2") (pintype "passive"))
      (node (ref "J10") (pin "5") (pinfunction "5_5") (pintype "passive"))
      (node (ref "J10") (pin "6") (pinfunction "6_6") (pintype "passive"))
      (node (ref "RV2") (pin "3") (pinfunction "E_3") (pintype "passive"))
    )
    (net (code "65") (name "RAMPOUT") (class "Default")
      (node (ref "J1") (pin "7") (pinfunction "7_7") (pintype "passive"))
      (node (ref "J10") (pin "10") (pinfunction "10_10") (pintype "passive"))
      (node (ref "J10") (pin "9") (pinfunction "9_9") (pintype "passive"))
      (node (ref "R36") (pin "2") (pinfunction "2_2") (pintype "passive"))
      (node (ref "U2") (pin "8") (pinfunction "3OUT_8") (pintype "output"))
      (node (ref "U2") (pin "9") (pinfunction "3IN-_9") (pintype "input"))
    )
    (net (code "66") (name "REF") (class "Default")
      (node (ref "J13") (pin "5") (pinfunction "5_5") (pintype "passive"))
      (node (ref "R21") (pin "2") (pinfunction "2_2") (pintype "passive"))
      (node (ref "RV3") (pin "2") (pinfunction "2_2") (pintype "passive"))
      (node (ref "TP1") (pin "TP") (pinfunction "TP_TP") (pintype "input"))
    )
    (net (code "67") (name "SQUAREOUT") (class "Default")
      (node (ref "J1") (pin "3") (pinfunction "3_3") (pintype "passive"))
      (node (ref "J10") (pin "7") (pinfunction "7_7") (pintype "passive"))
      (node (ref "J10") (pin "8") (pinfunction "8_8") (pintype "passive"))
      (node (ref "U1") (pin "1") (pinfunction "1OUT_1") (pintype "output"))
      (node (ref "U1") (pin "2") (pinfunction "1IN-_2") (pintype "input"))
    )
    (net (code "68") (name "SYNCIN1") (class "Default")
      (node (ref "C4") (pin "1") (pinfunction "1_1") (pintype "passive"))
      (node (ref "J1") (pin "6") (pinfunction "6_6") (pintype "passive"))
    )
    (net (code "69") (name "TRIANGLEOUT") (class "Default")
      (node (ref "J1") (pin "5") (pinfunction "5_5") (pintype "passive"))
      (node (ref "U2") (pin "13") (pinfunction "4IN-_13") (pintype "input"))
      (node (ref "U2") (pin "14") (pinfunction "4OUT_14") (pintype "output"))
    )
    (net (code "70") (name "TUNERPOWER") (class "Default")
      (node (ref "P1") (pin "10") (pinfunction "10_10") (pintype "passive"))
      (node (ref "P1") (pin "9") (pinfunction "9_9") (pintype "passive"))
      (node (ref "R27") (pin "2") (pinfunction "2_2") (pintype "passive"))
      (node (ref "R40") (pin "1") (pinfunction "1_1") (pintype "passive"))
    )
    (net (code "71") (name "VP") (class "Default")
      (node (ref "IC1") (pin "4") (pinfunction "4_4") (pintype "output"))
      (node (ref "R9") (pin "1") (pinfunction "1_1") (pintype "passive"))
      (node (ref "U1") (pin "3") (pinfunction "1IN_+_3") (pintype "input"))
    )
    (net (code "72") (name "VPWM") (class "Default")
      (node (ref "IC1") (pin "5") (pinfunction "5_5") (pintype "input"))
      (node (ref "R14") (pin "2") (pinfunction "2_2") (pintype "passive"))
      (node (ref "R15") (pin "2") (pinfunction "2_2") (pintype "passive"))
      (node (ref "U1") (pin "7") (pinfunction "2OUT_7") (pintype "output"))
    )
    (net (code "73") (name "VSO") (class "Default")
      (node (ref "IC1") (pin "8") (pinfunction "8_8") (pintype "output"))
      (node (ref "U2") (pin "10") (pinfunction "3IN+_10") (pintype "input"))
    )
    (net (code "74") (name "VTO") (class "Default")
      (node (ref "IC1") (pin "10") (pinfunction "10_10") (pintype "output"))
      (node (ref "U2") (pin "12") (pinfunction "4IN+_12") (pintype "input"))
    )
    (net (code "75") (name "unconnected-(ARDUINO_NANO1-3V3-Pad2)") (class "Default")
      (node (ref "ARDUINO_NANO1") (pin "2") (pinfunction "3V3_2") (pintype "output"))
    )
    (net (code "76") (name "unconnected-(ARDUINO_NANO1-A1-Pad5)") (class "Default")
      (node (ref "ARDUINO_NANO1") (pin "5") (pinfunction "A1_5") (pintype "bidirectional"))
    )
    (net (code "77") (name "unconnected-(ARDUINO_NANO1-A2-Pad6)") (class "Default")
      (node (ref "ARDUINO_NANO1") (pin "6") (pinfunction "A2_6") (pintype "bidirectional"))
    )
    (net (code "78") (name "unconnected-(ARDUINO_NANO1-A6-Pad10)") (class "Default")
      (node (ref "ARDUINO_NANO1") (pin "10") (pinfunction "A6_10") (pintype "bidirectional"))
    )
    (net (code "79") (name "unconnected-(ARDUINO_NANO1-A7-Pad11)") (class "Default")
      (node (ref "ARDUINO_NANO1") (pin "11") (pinfunction "A7_11") (pintype "bidirectional"))
    )
    (net (code "80") (name "unconnected-(ARDUINO_NANO1-AREF-Pad3)") (class "Default")
      (node (ref "ARDUINO_NANO1") (pin "3") (pinfunction "AREF_3") (pintype "input"))
    )
    (net (code "81") (name "unconnected-(ARDUINO_NANO1-D10-Pad28)") (class "Default")
      (node (ref "ARDUINO_NANO1") (pin "28") (pinfunction "D10_28") (pintype "bidirectional"))
    )
    (net (code "82") (name "unconnected-(ARDUINO_NANO1-D11-Pad29)") (class "Default")
      (node (ref "ARDUINO_NANO1") (pin "29") (pinfunction "D11_29") (pintype "bidirectional"))
    )
    (net (code "83") (name "unconnected-(ARDUINO_NANO1-D12-Pad30)") (class "Default")
      (node (ref "ARDUINO_NANO1") (pin "30") (pinfunction "D12_30") (pintype "bidirectional"))
    )
    (net (code "84") (name "unconnected-(ARDUINO_NANO1-D13-Pad1)") (class "Default")
      (node (ref "ARDUINO_NANO1") (pin "1") (pinfunction "D13_1") (pintype "bidirectional"))
    )
    (net (code "85") (name "unconnected-(ARDUINO_NANO1-RX0-Pad17)") (class "Default")
      (node (ref "ARDUINO_NANO1") (pin "17") (pinfunction "RX0_17") (pintype "bidirectional"))
    )
    (net (code "86") (name "unconnected-(ARDUINO_NANO1-TX1-Pad16)") (class "Default")
      (node (ref "ARDUINO_NANO1") (pin "16") (pinfunction "TX1_16") (pintype "bidirectional"))
    )
    (net (code "87") (name "unconnected-(ARDUINO_NANO1-~{RESET}-Pad13)") (class "Default")
      (node (ref "ARDUINO_NANO1") (pin "13") (pinfunction "~{RESET}_13") (pintype "input"))
    )
    (net (code "88") (name "unconnected-(ARDUINO_NANO1-~{RESET}-Pad18)") (class "Default")
      (node (ref "ARDUINO_NANO1") (pin "18") (pinfunction "~{RESET}_18") (pintype "input"))
    )
    (net (code "89") (name "unconnected-(IC1-Pad9)") (class "Default")
      (node (ref "IC1") (pin "9") (pinfunction "9_9") (pintype "input"))
    )
  )
)
